# switches.net
KiCad netlist of a schematic drawn in Altium Designer
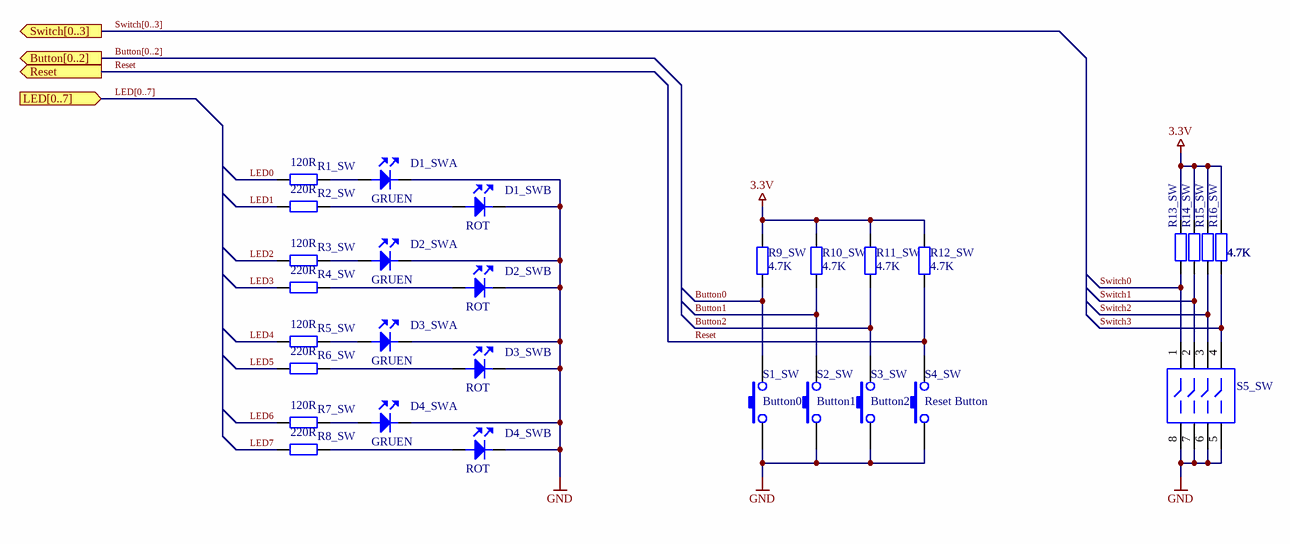
[diagram p0: switches.SchDoc]

(export (version "E")
  (design (tool "Eeschema 10.0.6"))
  (components
    (comp (ref "D1_SW")
      (value "1211C-LED")
      (footprint "stan-led4")
      (description "Stanley 1211C Bi-Color Ultra Compact SMT LED")
      (fields (field (name "MANUFACTURER") "Stanley") (field (name "PART NUMBER") "BRBG1211C"))
      (libsource (lib "gecko3-user") (part "1211C-LED"))
    )
    (comp (ref "D2_SW")
      (value "1211C-LED")
      (footprint "stan-led4")
      (description "Stanley 1211C Bi-Color Ultra Compact SMT LED")
      (fields (field (name "MANUFACTURER") "Stanley") (field (name "PART NUMBER") "BRBG1211C"))
      (libsource (lib "gecko3-user") (part "1211C-LED"))
    )
    (comp (ref "D3_SW")
      (value "1211C-LED")
      (footprint "stan-led4")
      (description "Stanley 1211C Bi-Color Ultra Compact SMT LED")
      (fields (field (name "MANUFACTURER") "Stanley") (field (name "PART NUMBER") "BRBG1211C"))
      (libsource (lib "gecko3-user") (part "1211C-LED"))
    )
    (comp (ref "D4_SW")
      (value "1211C-LED")
      (footprint "stan-led4")
      (description "Stanley 1211C Bi-Color Ultra Compact SMT LED")
      (fields (field (name "MANUFACTURER") "Stanley") (field (name "PART NUMBER") "BRBG1211C"))
      (libsource (lib "gecko3-user") (part "1211C-LED"))
    )
    (comp (ref "R1_SW")
      (value "120R")
      (footprint "0402")
      (description "Resistor")
      (fields
        (field (name "MANUFACTURER") "PHYCOMP")
        (field (name "PART NUMBER") "232270671201")
        (field (name "PUBLISHER") "Altium Limited")
      )
      (libsource (lib "Miscellaneous Devices") (part "Res2"))
    )
    (comp (ref "R2_SW")
      (value "220R")
      (footprint "0402")
      (description "Resistor")
      (fields
        (field (name "MANUFACTURER") "PHYCOMP")
        (field (name "PART NUMBER") "232270672201")
        (field (name "PUBLISHER") "Altium Limited")
      )
      (libsource (lib "Miscellaneous Devices") (part "Res2"))
    )
    (comp (ref "R3_SW")
      (value "120R")
      (footprint "0402")
      (description "Resistor")
      (fields
        (field (name "MANUFACTURER") "PHYCOMP")
        (field (name "PART NUMBER") "232270671201")
        (field (name "PUBLISHER") "Altium Limited")
      )
      (libsource (lib "Miscellaneous Devices") (part "Res2"))
    )
    (comp (ref "R4_SW")
      (value "220R")
      (footprint "0402")
      (description "Resistor")
      (fields
        (field (name "MANUFACTURER") "PHYCOMP")
        (field (name "PART NUMBER") "232270672201")
        (field (name "PUBLISHER") "Altium Limited")
      )
      (libsource (lib "Miscellaneous Devices") (part "Res2"))
    )
    (comp (ref "R5_SW")
      (value "120R")
      (footprint "0402")
      (description "Resistor")
      (fields
        (field (name "MANUFACTURER") "PHYCOMP")
        (field (name "PART NUMBER") "232270671201")
        (field (name "PUBLISHER") "Altium Limited")
      )
      (libsource (lib "Miscellaneous Devices") (part "Res2"))
    )
    (comp (ref "R6_SW")
      (value "220R")
      (footprint "0402")
      (description "Resistor")
      (fields
        (field (name "MANUFACTURER") "PHYCOMP")
        (field (name "PART NUMBER") "232270672201")
        (field (name "PUBLISHER") "Altium Limited")
      )
      (libsource (lib "Miscellaneous Devices") (part "Res2"))
    )
    (comp (ref "R7_SW")
      (value "120R")
      (footprint "0402")
      (description "Resistor")
      (fields
        (field (name "MANUFACTURER") "PHYCOMP")
        (field (name "PART NUMBER") "232270671201")
        (field (name "PUBLISHER") "Altium Limited")
      )
      (libsource (lib "Miscellaneous Devices") (part "Res2"))
    )
    (comp (ref "R8_SW")
      (value "220R")
      (footprint "0402")
      (description "Resistor")
      (fields
        (field (name "MANUFACTURER") "PHYCOMP")
        (field (name "PART NUMBER") "232270672201")
        (field (name "PUBLISHER") "Altium Limited")
      )
      (libsource (lib "Miscellaneous Devices") (part "Res2"))
    )
    (comp (ref "R9_SW")
      (value "4.7K")
      (footprint "0402")
      (description "Resistor")
      (fields
        (field (name "MANUFACTURER") "PHYCOMP")
        (field (name "PART NUMBER") "232270674702")
        (field (name "PUBLISHER") "Altium Limited")
      )
      (libsource (lib "Miscellaneous Devices") (part "Res2"))
    )
    (comp (ref "R10_SW")
      (value "4.7K")
      (footprint "0402")
      (description "Resistor")
      (fields
        (field (name "MANUFACTURER") "PHYCOMP")
        (field (name "PART NUMBER") "232270674702")
        (field (name "PUBLISHER") "Altium Limited")
      )
      (libsource (lib "Miscellaneous Devices") (part "Res2"))
    )
    (comp (ref "R11_SW")
      (value "4.7K")
      (footprint "0402")
      (description "Resistor")
      (fields
        (field (name "MANUFACTURER") "PHYCOMP")
        (field (name "PART NUMBER") "232270674702")
        (field (name "PUBLISHER") "Altium Limited")
      )
      (libsource (lib "Miscellaneous Devices") (part "Res2"))
    )
    (comp (ref "R12_SW")
      (value "4.7K")
      (footprint "0402")
      (description "Resistor")
      (fields
        (field (name "MANUFACTURER") "PHYCOMP")
        (field (name "PART NUMBER") "232270674702")
        (field (name "PUBLISHER") "Altium Limited")
      )
      (libsource (lib "") (part "Res2_2"))
    )
    (comp (ref "R13_SW")
      (value "4.7K")
      (footprint "0402")
      (description "Resistor")
      (fields
        (field (name "MANUFACTURER") "PHYCOMP")
        (field (name "PART NUMBER") "232270674702")
        (field (name "PUBLISHER") "Altium Limited")
      )
      (libsource (lib "") (part "Res2_1"))
    )
    (comp (ref "R14_SW")
      (value "4.7K")
      (footprint "0402")
      (description "Resistor")
      (fields
        (field (name "MANUFACTURER") "PHYCOMP")
        (field (name "PART NUMBER") "232270674702")
        (field (name "PUBLISHER") "Altium Limited")
      )
      (libsource (lib "") (part "Res2_1"))
    )
    (comp (ref "R15_SW")
      (value "4.7K")
      (footprint "0402")
      (description "Resistor")
      (fields
        (field (name "MANUFACTURER") "PHYCOMP")
        (field (name "PART NUMBER") "232270674702")
        (field (name "PUBLISHER") "Altium Limited")
      )
      (libsource (lib "") (part "Res2_1"))
    )
    (comp (ref "R16_SW")
      (value "4.7K")
      (footprint "0402")
      (description "Resistor")
      (fields
        (field (name "MANUFACTURER") "PHYCOMP")
        (field (name "PART NUMBER") "232270674702")
        (field (name "PUBLISHER") "Altium Limited")
      )
      (libsource (lib "") (part "Res2_1"))
    )
    (comp (ref "S1_SW")
      (value "Button0")
      (footprint "FSM")
      (fields (field (name "MANUFACTURER") "TYCO") (field (name "PART NUMBER") "0-1437565-1"))
      (libsource (lib "gecko3-user") (part "SW_PB"))
    )
    (comp (ref "S2_SW")
      (value "Button1")
      (footprint "FSM")
      (fields (field (name "MANUFACTURER") "TYCO") (field (name "PART NUMBER") "0-1437565-1"))
      (libsource (lib "gecko3-user") (part "SW_PB"))
    )
    (comp (ref "S3_SW")
      (value "Button2")
      (footprint "FSM")
      (fields (field (name "MANUFACTURER") "TYCO") (field (name "PART NUMBER") "0-1437565-1"))
      (libsource (lib "gecko3-user") (part "SW_PB"))
    )
    (comp (ref "S4_SW")
      (value "Reset Button")
      (footprint "FSM")
      (fields (field (name "MANUFACTURER") "TYCO") (field (name "PART NUMBER") "0-1437565-1"))
      (libsource (lib "gecko3-user") (part "SW_PB"))
    )
    (comp (ref "S5_SW")
      (value "SW-DIP4")
      (footprint "DIP4")
      (fields (field (name "MANUFACTURER") "Diptronics") (field (name "PART NUMBER") "PM-040900"))
      (libsource (lib "gecko3-user") (part "SW-DIP4"))
    )
  )
  (nets
    (net (code "1") (name "/Button0") (class "Default")
      (node (ref "R9_SW") (pin "2") (pinfunction "2_2") (pintype "passive"))
      (node (ref "S1_SW") (pin "1") (pinfunction "1_1") (pintype "passive"))
    )
    (net (code "2") (name "/Button1") (class "Default")
      (node (ref "R10_SW") (pin "2") (pinfunction "2_2") (pintype "passive"))
      (node (ref "S2_SW") (pin "1") (pinfunction "1_1") (pintype "passive"))
    )
    (net (code "3") (name "/Button2") (class "Default")
      (node (ref "R11_SW") (pin "2") (pinfunction "2_2") (pintype "passive"))
      (node (ref "S3_SW") (pin "1") (pinfunction "1_1") (pintype "passive"))
    )
    (net (code "5") (name "/LED0") (class "Default")
      (node (ref "R1_SW") (pin "2") (pinfunction "2_2") (pintype "passive"))
    )
    (net (code "6") (name "/LED1") (class "Default")
      (node (ref "R2_SW") (pin "2") (pinfunction "2_2") (pintype "passive"))
    )
    (net (code "7") (name "/LED2") (class "Default")
      (node (ref "R3_SW") (pin "2") (pinfunction "2_2") (pintype "passive"))
    )
    (net (code "8") (name "/LED3") (class "Default")
      (node (ref "R4_SW") (pin "2") (pinfunction "2_2") (pintype "passive"))
    )
    (net (code "9") (name "/LED4") (class "Default")
      (node (ref "R5_SW") (pin "2") (pinfunction "2_2") (pintype "passive"))
    )
    (net (code "10") (name "/LED5") (class "Default")
      (node (ref "R6_SW") (pin "2") (pinfunction "2_2") (pintype "passive"))
    )
    (net (code "11") (name "/LED6") (class "Default")
      (node (ref "R7_SW") (pin "2") (pinfunction "2_2") (pintype "passive"))
    )
    (net (code "12") (name "/LED7") (class "Default")
      (node (ref "R8_SW") (pin "2") (pinfunction "2_2") (pintype "passive"))
    )
    (net (code "14") (name "/Reset") (class "Default")
      (node (ref "R12_SW") (pin "2") (pinfunction "2_2") (pintype "passive"))
      (node (ref "S4_SW") (pin "2") (pinfunction "2_2") (pintype "passive"))
    )
    (net (code "15") (name "/Switch0") (class "Default")
      (node (ref "R13_SW") (pin "1") (pinfunction "1_1") (pintype "passive"))
      (node (ref "S5_SW") (pin "1") (pinfunction "1_1") (pintype "passive"))
    )
    (net (code "16") (name "/Switch1") (class "Default")
      (node (ref "R14_SW") (pin "1") (pinfunction "1_1") (pintype "passive"))
      (node (ref "S5_SW") (pin "2") (pinfunction "2_2") (pintype "passive"))
    )
    (net (code "17") (name "/Switch2") (class "Default")
      (node (ref "R15_SW") (pin "1") (pinfunction "1_1") (pintype "passive"))
      (node (ref "S5_SW") (pin "3") (pinfunction "3_3") (pintype "passive"))
    )
    (net (code "18") (name "/Switch3") (class "Default")
      (node (ref "R16_SW") (pin "1") (pinfunction "1_1") (pintype "passive"))
      (node (ref "S5_SW") (pin "4") (pinfunction "4_4") (pintype "passive"))
    )
    (net (code "20") (name "3.3V") (class "Default")
      (node (ref "R10_SW") (pin "1") (pinfunction "1_1") (pintype "passive"))
      (node (ref "R11_SW") (pin "1") (pinfunction "1_1") (pintype "passive"))
      (node (ref "R12_SW") (pin "1") (pinfunction "1_1") (pintype "passive"))
      (node (ref "R13_SW") (pin "2") (pinfunction "2_2") (pintype "passive"))
      (node (ref "R14_SW") (pin "2") (pinfunction "2_2") (pintype "passive"))
      (node (ref "R15_SW") (pin "2") (pinfunction "2_2") (pintype "passive"))
      (node (ref "R16_SW") (pin "2") (pinfunction "2_2") (pintype "passive"))
      (node (ref "R9_SW") (pin "1") (pinfunction "1_1") (pintype "passive"))
    )
    (net (code "21") (name "GND") (class "Default")
      (node (ref "D1_SW") (pin "2") (pinfunction "K_2") (pintype "passive"))
      (node (ref "D1_SW") (pin "4") (pinfunction "K_4") (pintype "passive"))
      (node (ref "D2_SW") (pin "2") (pinfunction "K_2") (pintype "passive"))
      (node (ref "D2_SW") (pin "4") (pinfunction "K_4") (pintype "passive"))
      (node (ref "D3_SW") (pin "2") (pinfunction "K_2") (pintype "passive"))
      (node (ref "D3_SW") (pin "4") (pinfunction "K_4") (pintype "passive"))
      (node (ref "D4_SW") (pin "2") (pinfunction "K_2") (pintype "passive"))
      (node (ref "D4_SW") (pin "4") (pinfunction "K_4") (pintype "passive"))
      (node (ref "S1_SW") (pin "2") (pinfunction "2_2") (pintype "passive"))
      (node (ref "S2_SW") (pin "2") (pinfunction "2_2") (pintype "passive"))
      (node (ref "S3_SW") (pin "2") (pinfunction "2_2") (pintype "passive"))
      (node (ref "S4_SW") (pin "1") (pinfunction "1_1") (pintype "passive"))
      (node (ref "S5_SW") (pin "5") (pinfunction "5_5") (pintype "passive"))
      (node (ref "S5_SW") (pin "6") (pinfunction "6_6") (pintype "passive"))
      (node (ref "S5_SW") (pin "7") (pinfunction "7_7") (pintype "passive"))
      (node (ref "S5_SW") (pin "8") (pinfunction "8_8") (pintype "passive"))
    )
    (net (code "22") (name "Net-(D1_SWA-A)") (class "Default")
      (node (ref "D1_SW") (pin "3") (pinfunction "A_3") (pintype "passive"))
      (node (ref "R1_SW") (pin "1") (pinfunction "1_1") (pintype "passive"))
    )
    (net (code "23") (name "Net-(D1_SWB-A)") (class "Default")
      (node (ref "D1_SW") (pin "1") (pinfunction "A_1") (pintype "passive"))
      (node (ref "R2_SW") (pin "1") (pinfunction "1_1") (pintype "passive"))
    )
    (net (code "24") (name "Net-(D2_SWA-A)") (class "Default")
      (node (ref "D2_SW") (pin "3") (pinfunction "A_3") (pintype "passive"))
      (node (ref "R3_SW") (pin "1") (pinfunction "1_1") (pintype "passive"))
    )
    (net (code "25") (name "Net-(D2_SWB-A)") (class "Default")
      (node (ref "D2_SW") (pin "1") (pinfunction "A_1") (pintype "passive"))
      (node (ref "R4_SW") (pin "1") (pinfunction "1_1") (pintype "passive"))
    )
    (net (code "26") (name "Net-(D3_SWA-A)") (class "Default")
      (node (ref "D3_SW") (pin "3") (pinfunction "A_3") (pintype "passive"))
      (node (ref "R5_SW") (pin "1") (pinfunction "1_1") (pintype "passive"))
    )
    (net (code "27") (name "Net-(D3_SWB-A)") (class "Default")
      (node (ref "D3_SW") (pin "1") (pinfunction "A_1") (pintype "passive"))
      (node (ref "R6_SW") (pin "1") (pinfunction "1_1") (pintype "passive"))
    )
    (net (code "28") (name "Net-(D4_SWA-A)") (class "Default")
      (node (ref "D4_SW") (pin "3") (pinfunction "A_3") (pintype "passive"))
      (node (ref "R7_SW") (pin "1") (pinfunction "1_1") (pintype "passive"))
    )
    (net (code "29") (name "Net-(D4_SWB-A)") (class "Default")
      (node (ref "D4_SW") (pin "1") (pinfunction "A_1") (pintype "passive"))
      (node (ref "R8_SW") (pin "1") (pinfunction "1_1") (pintype "passive"))
    )
  )
)
